# uart_key.net
KiCad netlist of a schematic drawn in Altium Designer
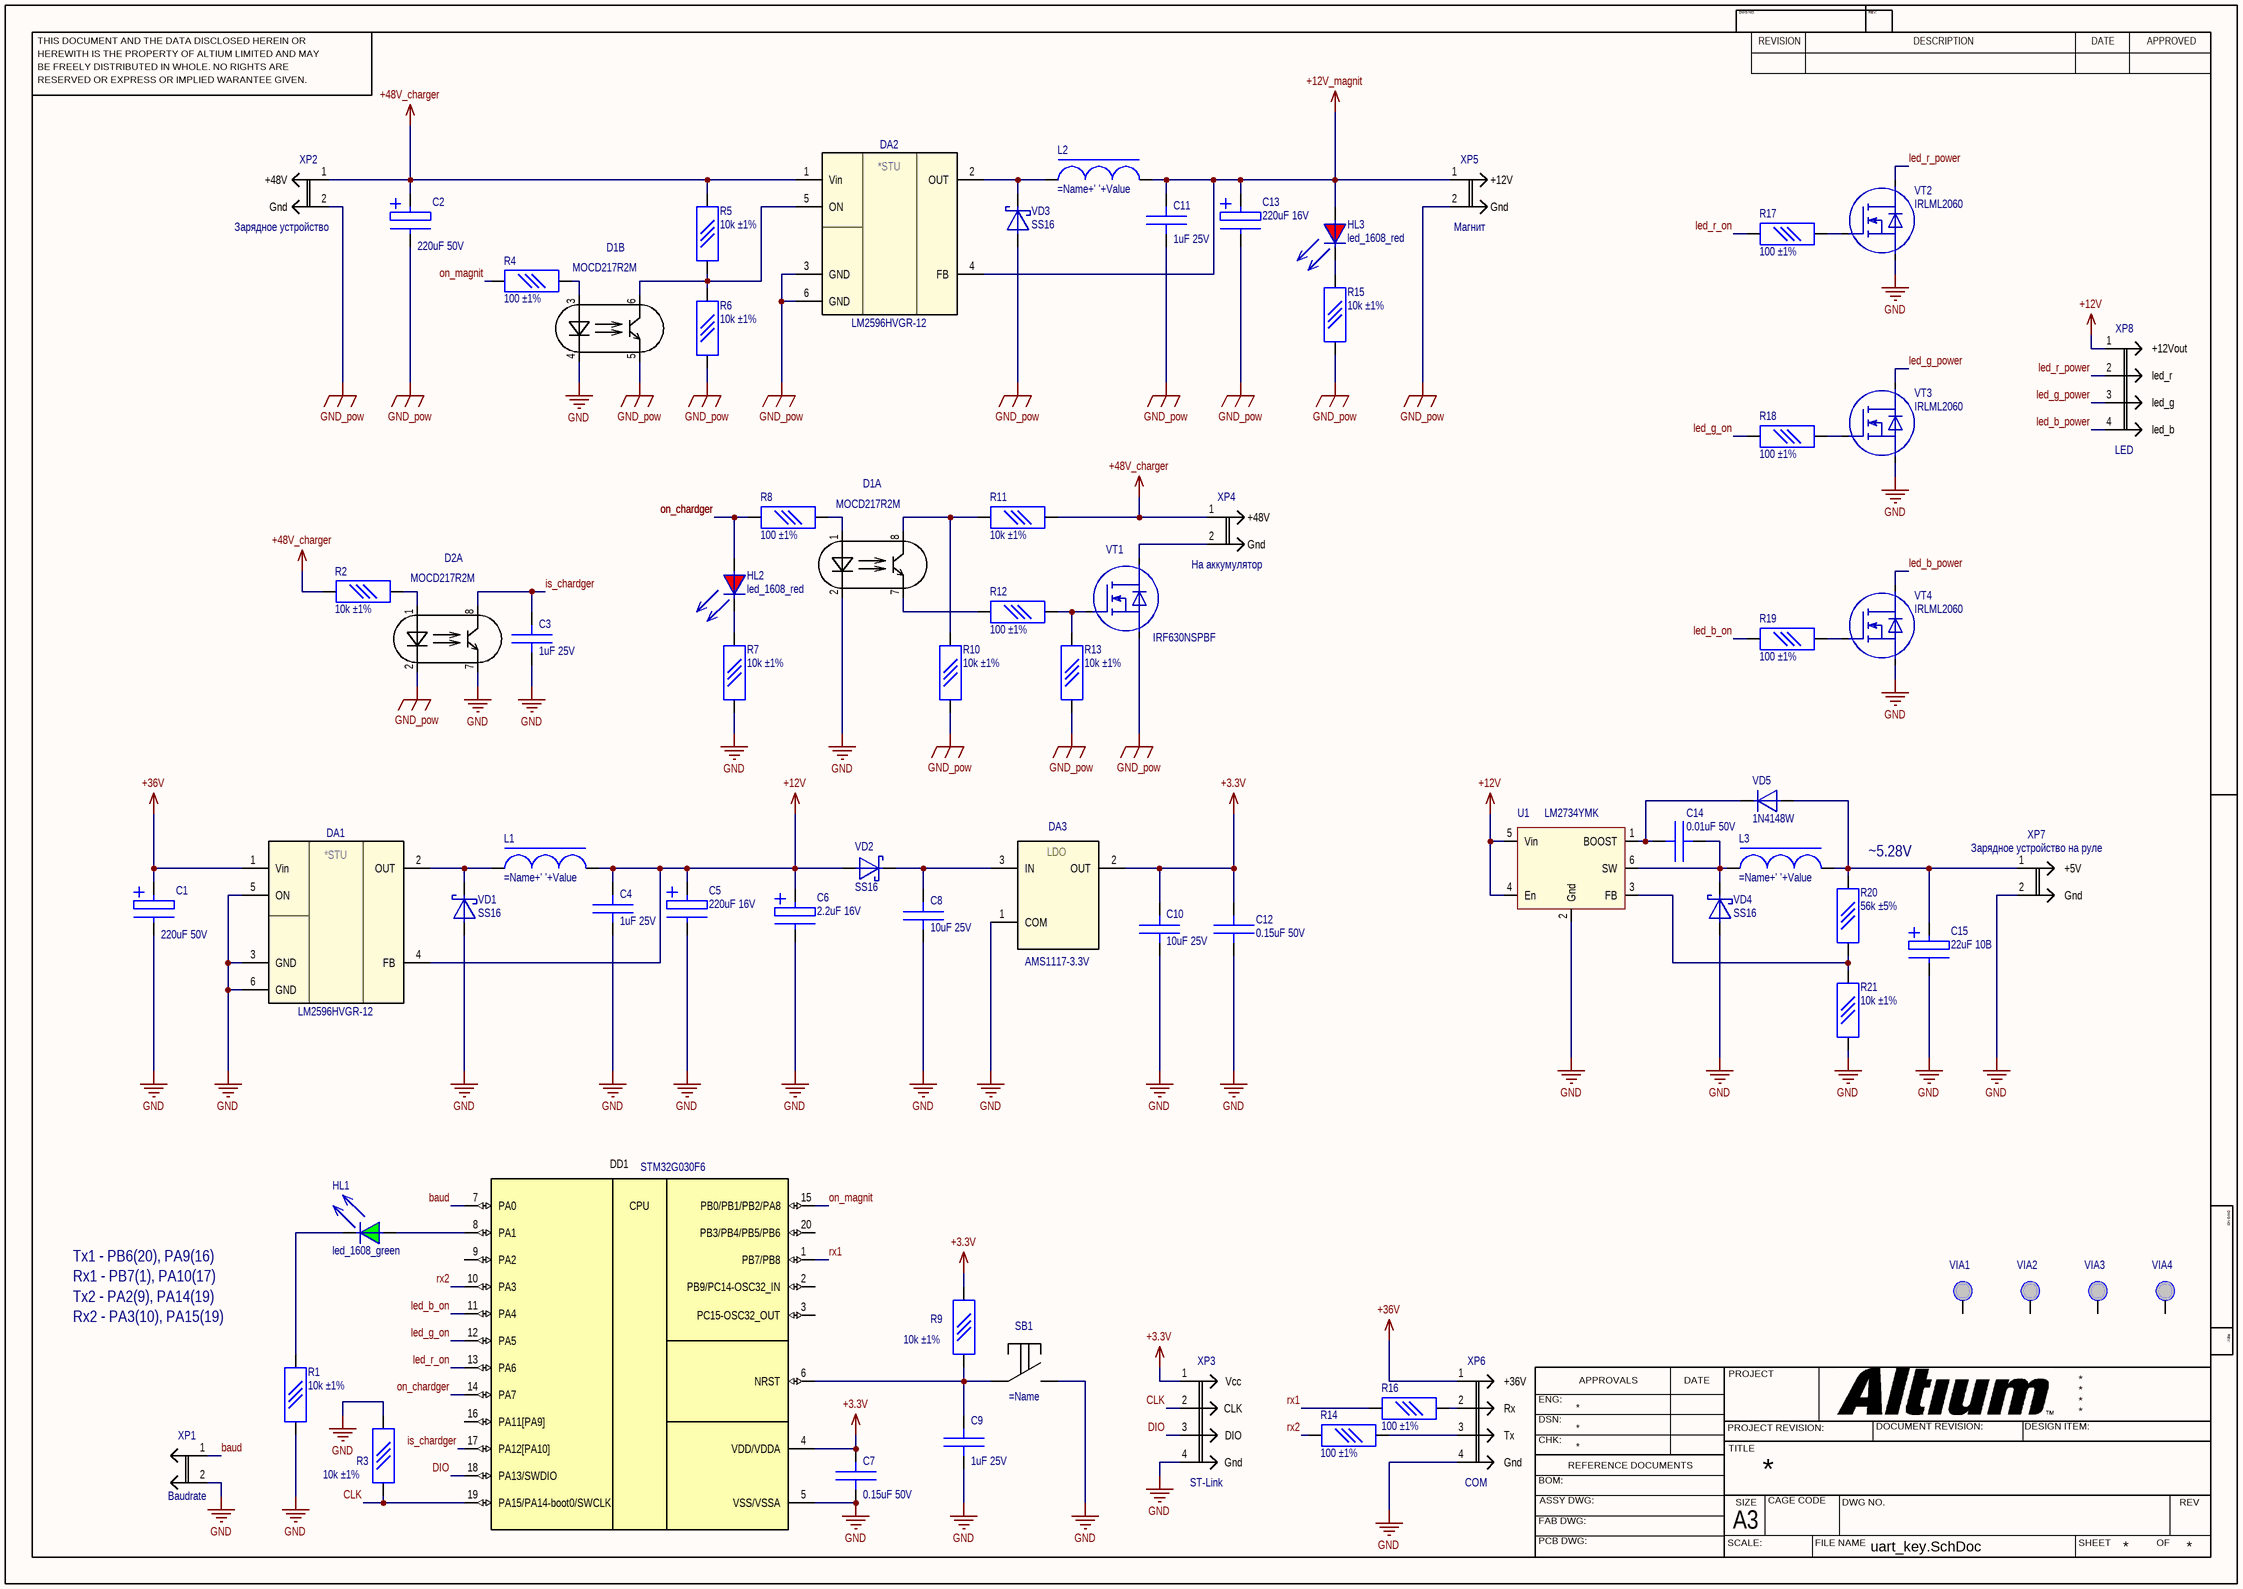
[diagram p0: uart_key.SchDoc]

(export (version "E")
  (design (tool "Eeschema 10.0.6"))
  (components
    (comp (ref "C1")
      (value "220uF 50V")
      (footprint "CAPAE_SMD_1010")
      (fields (field (name "VOLTAGE") "50V") (field (name "TOLERANCE") "±10%"))
      (libsource (lib "AD_lib") (part "Capacitor_elec"))
    )
    (comp (ref "C2")
      (value "220uF 50V")
      (footprint "CAPAE_SMD_1010")
      (fields (field (name "VOLTAGE") "50V") (field (name "TOLERANCE") "±10%"))
      (libsource (lib "AD_lib") (part "Capacitor_elec"))
    )
    (comp (ref "C3")
      (value "1uF 25V")
      (footprint "CC0603_0.8mm")
      (fields (field (name "VOLTAGE") "25V") (field (name "TOLERANCE") "±10%"))
      (libsource (lib "AD_lib") (part "Capacitor"))
    )
    (comp (ref "C4")
      (value "1uF 25V")
      (footprint "CC0603_0.8mm")
      (fields (field (name "VOLTAGE") "25V") (field (name "TOLERANCE") "±10%"))
      (libsource (lib "AD_lib") (part "Capacitor"))
    )
    (comp (ref "C5")
      (value "220uF 16V")
      (footprint "CAPAE_SMD_0607")
      (fields (field (name "VOLTAGE") "16V") (field (name "TOLERANCE") "±10%"))
      (libsource (lib "AD_lib") (part "Capacitor_elec"))
    )
    (comp (ref "C6")
      (value "2.2uF 16V")
      (footprint "TANT_3.2X1.6_A")
      (fields (field (name "VOLTAGE") "16V") (field (name "TOLERANCE") "±10%"))
      (libsource (lib "AD_lib") (part "Capacitor_elec"))
    )
    (comp (ref "C7")
      (value "0.15uF 50V")
      (footprint "CC0603_0.8mm")
      (fields (field (name "VOLTAGE") "50V") (field (name "TOLERANCE") "±10%"))
      (libsource (lib "AD_lib") (part "Capacitor"))
    )
    (comp (ref "C8")
      (value "10uF 25V")
      (footprint "CC0603_0.8mm")
      (fields (field (name "VOLTAGE") "25V") (field (name "TOLERANCE") "±10%"))
      (libsource (lib "AD_lib") (part "Capacitor"))
    )
    (comp (ref "C9")
      (value "1uF 25V")
      (footprint "CC0603_0.8mm")
      (fields (field (name "VOLTAGE") "25V") (field (name "TOLERANCE") "±10%"))
      (libsource (lib "AD_lib") (part "Capacitor"))
    )
    (comp (ref "C10")
      (value "10uF 25V")
      (footprint "CC0603_0.8mm")
      (fields (field (name "VOLTAGE") "25V") (field (name "TOLERANCE") "±10%"))
      (libsource (lib "AD_lib") (part "Capacitor"))
    )
    (comp (ref "C11")
      (value "1uF 25V")
      (footprint "CC0603_0.8mm")
      (fields (field (name "VOLTAGE") "25V") (field (name "TOLERANCE") "±10%"))
      (libsource (lib "AD_lib") (part "Capacitor"))
    )
    (comp (ref "C12")
      (value "0.15uF 50V")
      (footprint "CC0603_0.8mm")
      (fields (field (name "VOLTAGE") "50V") (field (name "TOLERANCE") "±10%"))
      (libsource (lib "AD_lib") (part "Capacitor"))
    )
    (comp (ref "C13")
      (value "220uF 16V")
      (footprint "CAPAE_SMD_0607")
      (fields (field (name "VOLTAGE") "16V") (field (name "TOLERANCE") "±10%"))
      (libsource (lib "AD_lib") (part "Capacitor_elec"))
    )
    (comp (ref "C14")
      (value "0.01uF 50V")
      (footprint "CC0603_0.8mm")
      (fields (field (name "VOLTAGE") "50V") (field (name "TOLERANCE") "±10%"))
      (libsource (lib "AD_lib") (part "Capacitor"))
    )
    (comp (ref "C15")
      (value "22uF 10В")
      (footprint "TANT_3.5X2.8_B")
      (fields (field (name "VOLTAGE") "10В") (field (name "TOLERANCE") "±10%"))
      (libsource (lib "AD_lib") (part "Capacitor_elec"))
    )
    (comp (ref "D1")
      (value "MOCD217R2M")
      (footprint "SO-8_height")
      (libsource (lib "AD_lib") (part "MOCD217R2M"))
    )
    (comp (ref "D2")
      (value "MOCD217R2M")
      (footprint "SO-8_height")
      (libsource (lib "AD_lib") (part "MOCD217R2M"))
    )
    (comp (ref "DA1")
      (value "LM2596HVGR-12")
      (footprint "TO-263-5 (D2PAK)_2_thermal_pad")
      (libsource (lib "AD_lib") (part "LM2596HVGR-12"))
    )
    (comp (ref "DA2")
      (value "LM2596HVGR-12")
      (footprint "TO-263-5 (D2PAK)_2_thermal_pad")
      (libsource (lib "AD_lib") (part "LM2596HVGR-12"))
    )
    (comp (ref "DA3")
      (value "AMS1117-3.3V")
      (footprint "SOT-223")
      (libsource (lib "AD_lib") (part "AMS1117-___V"))
    )
    (comp (ref "DD1")
      (value "STM32G030F6")
      (footprint "TSSOP-20_ST")
      (libsource (lib "AD_lib") (part "STM32G030F6"))
    )
    (comp (ref "HL1")
      (value "led_1608_green")
      (footprint "led_1608")
      (libsource (lib "AD_lib") (part "led_1608_green"))
    )
    (comp (ref "HL2")
      (value "led_1608_red")
      (footprint "led_1608")
      (libsource (lib "AD_lib") (part "led_1608_red"))
    )
    (comp (ref "HL3")
      (value "led_1608_red")
      (footprint "led_1608")
      (libsource (lib "AD_lib") (part "led_1608_red"))
    )
    (comp (ref "L1") (value "33uH") (footprint "SDR1006") (libsource (lib "AD_lib") (part "Inductor")))
    (comp (ref "L2") (value "33uH") (footprint "SDR1006") (libsource (lib "AD_lib") (part "Inductor")))
    (comp (ref "L3") (value "10uH") (footprint "SDR0604") (libsource (lib "AD_lib") (part "Inductor")))
    (comp (ref "R1")
      (value "10k ±1%")
      (footprint "R0603")
      (fields (field (name "TOLERANCE") "±1%"))
      (libsource (lib "AD_lib") (part "Res_0603"))
    )
    (comp (ref "R2")
      (value "10k ±1%")
      (footprint "R0603")
      (fields (field (name "TOLERANCE") "±1%"))
      (libsource (lib "AD_lib") (part "Res_0603"))
    )
    (comp (ref "R3")
      (value "10k ±1%")
      (footprint "R0603")
      (fields (field (name "TOLERANCE") "±1%"))
      (libsource (lib "AD_lib") (part "Res_0603"))
    )
    (comp (ref "R4")
      (value "100 ±1%")
      (footprint "R0603")
      (fields (field (name "TOLERANCE") "±1%"))
      (libsource (lib "AD_lib") (part "Res_0603"))
    )
    (comp (ref "R5")
      (value "10k ±1%")
      (footprint "R0603")
      (fields (field (name "TOLERANCE") "±1%"))
      (libsource (lib "AD_lib") (part "Res_0603"))
    )
    (comp (ref "R6")
      (value "10k ±1%")
      (footprint "R0603")
      (fields (field (name "TOLERANCE") "±1%"))
      (libsource (lib "AD_lib") (part "Res_0603"))
    )
    (comp (ref "R7")
      (value "10k ±1%")
      (footprint "R0603")
      (fields (field (name "TOLERANCE") "±1%"))
      (libsource (lib "AD_lib") (part "Res_0603"))
    )
    (comp (ref "R8")
      (value "100 ±1%")
      (footprint "R0603")
      (fields (field (name "TOLERANCE") "±1%"))
      (libsource (lib "AD_lib") (part "Res_0603"))
    )
    (comp (ref "R9")
      (value "10k ±1%")
      (footprint "R0603")
      (fields (field (name "TOLERANCE") "±1%"))
      (libsource (lib "AD_lib") (part "Res_0603"))
    )
    (comp (ref "R10")
      (value "10k ±1%")
      (footprint "R0603")
      (fields (field (name "TOLERANCE") "±1%"))
      (libsource (lib "AD_lib") (part "Res_0603"))
    )
    (comp (ref "R11")
      (value "10k ±1%")
      (footprint "R0603")
      (fields (field (name "TOLERANCE") "±1%"))
      (libsource (lib "AD_lib") (part "Res_0603"))
    )
    (comp (ref "R12")
      (value "100 ±1%")
      (footprint "R0603")
      (fields (field (name "TOLERANCE") "±1%"))
      (libsource (lib "AD_lib") (part "Res_0603"))
    )
    (comp (ref "R13")
      (value "10k ±1%")
      (footprint "R0603")
      (fields (field (name "TOLERANCE") "±1%"))
      (libsource (lib "AD_lib") (part "Res_0603"))
    )
    (comp (ref "R14")
      (value "100 ±1%")
      (footprint "R0603")
      (fields (field (name "TOLERANCE") "±1%"))
      (libsource (lib "AD_lib") (part "Res_0603"))
    )
    (comp (ref "R15")
      (value "10k ±1%")
      (footprint "R0603")
      (fields (field (name "TOLERANCE") "±1%"))
      (libsource (lib "AD_lib") (part "Res_0603"))
    )
    (comp (ref "R16")
      (value "100 ±1%")
      (footprint "R0603")
      (fields (field (name "TOLERANCE") "±1%"))
      (libsource (lib "AD_lib") (part "Res_0603"))
    )
    (comp (ref "R17")
      (value "100 ±1%")
      (footprint "R0603")
      (fields (field (name "TOLERANCE") "±1%"))
      (libsource (lib "AD_lib") (part "Res_0603"))
    )
    (comp (ref "R18")
      (value "100 ±1%")
      (footprint "R0603")
      (fields (field (name "TOLERANCE") "±1%"))
      (libsource (lib "AD_lib") (part "Res_0603"))
    )
    (comp (ref "R19")
      (value "100 ±1%")
      (footprint "R0603")
      (fields (field (name "TOLERANCE") "±1%"))
      (libsource (lib "AD_lib") (part "Res_0603"))
    )
    (comp (ref "R20")
      (value "56k ±5%")
      (footprint "R0603")
      (fields (field (name "TOLERANCE") "±5%"))
      (libsource (lib "AD_lib") (part "Res_0603"))
    )
    (comp (ref "R21")
      (value "10k ±1%")
      (footprint "R0603")
      (fields (field (name "TOLERANCE") "±1%"))
      (libsource (lib "AD_lib") (part "Res_0603"))
    )
    (comp (ref "SB1")
      (value "~")
      (footprint "KLS7-TS3401_4х3х2,5")
      (libsource (lib "AD_lib") (part "Tact_4х3х2.5_SMD"))
    )
    (comp (ref "U1") (value "LM2734YMK") (footprint "SOT-23-6") (libsource (lib "AD_lib") (part "LM2734YMK")))
    (comp (ref "VD1") (value "SS16") (footprint "DO-214AC (SMA)") (libsource (lib "AD_lib") (part "SS16")))
    (comp (ref "VD2") (value "SS16") (footprint "DO-214AC (SMA)") (libsource (lib "AD_lib") (part "SS16")))
    (comp (ref "VD3") (value "SS16") (footprint "DO-214AC (SMA)") (libsource (lib "AD_lib") (part "SS16")))
    (comp (ref "VD4") (value "SS16") (footprint "DO-214AC (SMA)") (libsource (lib "AD_lib") (part "SS16")))
    (comp (ref "VD5") (value "1N4148W") (footprint "SOD-123") (libsource (lib "AD_lib") (part "Diode")))
    (comp (ref "VIA1")
      (value "via_circle_2.2mm")
      (footprint "via_circle_2.2")
      (libsource (lib "AD_lib") (part "via_circle_2.2mm"))
    )
    (comp (ref "VIA2")
      (value "via_circle_2.2mm")
      (footprint "via_circle_2.2")
      (libsource (lib "AD_lib") (part "via_circle_2.2mm"))
    )
    (comp (ref "VIA3")
      (value "via_circle_2.2mm")
      (footprint "via_circle_2.2")
      (libsource (lib "AD_lib") (part "via_circle_2.2mm"))
    )
    (comp (ref "VIA4")
      (value "via_circle_2.2mm")
      (footprint "via_circle_2.2")
      (libsource (lib "AD_lib") (part "via_circle_2.2mm"))
    )
    (comp (ref "VT1")
      (value "IRF630NSPBF")
      (footprint "TO-263A (D2PAK)_thermal_pad")
      (libsource (lib "AD_lib") (part "IRF630NSPBF"))
    )
    (comp (ref "VT2") (value "IRLML2060") (footprint "SOT-23") (libsource (lib "AD_lib") (part "IRLML2060")))
    (comp (ref "VT3") (value "IRLML2060") (footprint "SOT-23") (libsource (lib "AD_lib") (part "IRLML2060")))
    (comp (ref "VT4") (value "IRLML2060") (footprint "SOT-23") (libsource (lib "AD_lib") (part "IRLML2060")))
    (comp (ref "XP1")
      (value "Baudrate")
      (footprint "PLS-2")
      (libsource (lib "AD_lib") (part "Conn_01_02pin"))
    )
    (comp (ref "XP2")
      (value "Зарядное устройство")
      (footprint "DG308x2")
      (fields (field (name "CIRCUIT_1") "+48V") (field (name "CIRCUIT_2") "Gnd"))
      (libsource (lib "AD_lib") (part "DG308x2"))
    )
    (comp (ref "XP3")
      (value "ST-Link")
      (footprint "B4B-ZR")
      (fields
        (field (name "CIRCUIT_1") "Vcc")
        (field (name "CIRCUIT_2") "CLK")
        (field (name "CIRCUIT_3") "DIO")
        (field (name "CIRCUIT_4") "Gnd")
      )
      (libsource (lib "AD_lib") (part "B4B-ZR_conn_01x04_st_link"))
    )
    (comp (ref "XP4")
      (value "На аккумулятор")
      (footprint "DG308x2")
      (fields (field (name "CIRCUIT_1") "+48V") (field (name "CIRCUIT_2") "Gnd"))
      (libsource (lib "AD_lib") (part "DG308x2"))
    )
    (comp (ref "XP5")
      (value "Магнит")
      (footprint "DG308x2")
      (fields (field (name "CIRCUIT_1") "+12V") (field (name "CIRCUIT_2") "Gnd"))
      (libsource (lib "AD_lib") (part "DG308x2"))
    )
    (comp (ref "XP6")
      (value "COM")
      (footprint "JST_XH_B4B-XH-A_1x04_P2.50mm_Vertical")
      (fields
        (field (name "CIRCUIT_1") "+36V")
        (field (name "CIRCUIT_2") "Rx")
        (field (name "CIRCUIT_3") "Tx")
        (field (name "CIRCUIT_4") "Gnd")
      )
      (libsource (lib "AD_lib") (part "JST_XH_B4B-XH-A_1x04_P2.50mm_Vertical"))
    )
    (comp (ref "XP7")
      (value "Зарядное устройство на руле")
      (footprint "B2B-XH-A")
      (fields (field (name "+5V") "+5V") (field (name "CIRCUIT_2") "Gnd"))
      (libsource (lib "AD_lib") (part "Conn_01_02pin"))
    )
    (comp (ref "XP8")
      (value "LED")
      (footprint "JST_XH_B4B-XH-A_1x04_P2.50mm_Vertical")
      (fields
        (field (name "CIRCUIT_1") "+12Vout")
        (field (name "CIRCUIT_2") "led_r")
        (field (name "CIRCUIT_3") "led_g")
        (field (name "CIRCUIT_4") "led_b")
      )
      (libsource (lib "AD_lib") (part "JST_XH_B4B-XH-A_1x04_P2.50mm_Vertical"))
    )
  )
  (nets
    (net (code "1") (name "+3.3V") (class "Default")
      (node (ref "C10") (pin "1") (pintype "passive"))
      (node (ref "C12") (pin "1") (pintype "passive"))
      (node (ref "C7") (pin "1") (pintype "passive"))
      (node (ref "DA3") (pin "2") (pinfunction "OUT_2") (pintype "passive"))
      (node (ref "DD1") (pin "4") (pinfunction "VDD/VDDA_4") (pintype "power_in"))
      (node (ref "R9") (pin "1") (pinfunction "BOT_1") (pintype "passive"))
      (node (ref "XP3") (pin "1") (pinfunction "1_1") (pintype "passive"))
    )
    (net (code "2") (name "+12V") (class "Default")
      (node (ref "C4") (pin "1") (pintype "passive"))
      (node (ref "C5") (pin "2") (pinfunction "+_2") (pintype "passive"))
      (node (ref "C6") (pin "2") (pinfunction "+_2") (pintype "passive"))
      (node (ref "DA1") (pin "4") (pinfunction "FB_4") (pintype "passive"))
      (node (ref "L1") (pin "2") (pintype "passive"))
      (node (ref "U1") (pin "4") (pinfunction "En_4") (pintype "passive"))
      (node (ref "U1") (pin "5") (pinfunction "Vin_5") (pintype "passive"))
      (node (ref "VD2") (pin "2") (pinfunction "A_2") (pintype "passive"))
      (node (ref "XP8") (pin "1") (pinfunction "1_1") (pintype "passive"))
    )
    (net (code "3") (name "+12V_magnit") (class "Default")
      (node (ref "C11") (pin "1") (pintype "passive"))
      (node (ref "C13") (pin "2") (pinfunction "+_2") (pintype "passive"))
      (node (ref "DA2") (pin "4") (pinfunction "FB_4") (pintype "passive"))
      (node (ref "HL3") (pin "2") (pinfunction "A_2") (pintype "passive"))
      (node (ref "L2") (pin "2") (pintype "passive"))
      (node (ref "XP5") (pin "1") (pinfunction "1_1") (pintype "passive"))
    )
    (net (code "4") (name "+36V") (class "Default")
      (node (ref "C1") (pin "2") (pinfunction "+_2") (pintype "passive"))
      (node (ref "DA1") (pin "1") (pinfunction "Vin_1") (pintype "passive"))
      (node (ref "XP6") (pin "1") (pinfunction "1_1") (pintype "passive"))
    )
    (net (code "5") (name "+48V_charger") (class "Default")
      (node (ref "C2") (pin "2") (pinfunction "+_2") (pintype "passive"))
      (node (ref "DA2") (pin "1") (pinfunction "Vin_1") (pintype "passive"))
      (node (ref "R11") (pin "2") (pinfunction "TOP_2") (pintype "passive"))
      (node (ref "R2") (pin "2") (pinfunction "TOP_2") (pintype "passive"))
      (node (ref "R5") (pin "1") (pinfunction "BOT_1") (pintype "passive"))
      (node (ref "XP2") (pin "1") (pinfunction "1_1") (pintype "passive"))
      (node (ref "XP4") (pin "1") (pinfunction "1_1") (pintype "passive"))
    )
    (net (code "6") (name "/CLK") (class "Default")
      (node (ref "DD1") (pin "19") (pinfunction "PA15/PA14-boot0/SWCLK_19") (pintype "bidirectional"))
      (node (ref "R3") (pin "2") (pinfunction "TOP_2") (pintype "passive"))
      (node (ref "XP3") (pin "2") (pinfunction "2_2") (pintype "passive"))
    )
    (net (code "7") (name "/DIO") (class "Default")
      (node (ref "DD1") (pin "18") (pinfunction "PA13/SWDIO_18") (pintype "bidirectional"))
      (node (ref "XP3") (pin "3") (pinfunction "3_3") (pintype "passive"))
    )
    (net (code "8") (name "/baud") (class "Default")
      (node (ref "DD1") (pin "7") (pinfunction "PA0_7") (pintype "bidirectional"))
      (node (ref "XP1") (pin "1") (pinfunction "1_1") (pintype "passive"))
    )
    (net (code "9") (name "/is_chardger") (class "Default")
      (node (ref "C3") (pin "1") (pintype "passive"))
      (node (ref "D2") (pin "8") (pinfunction "8_8") (pintype "passive"))
      (node (ref "DD1") (pin "17") (pinfunction "PA12[PA10]_17") (pintype "bidirectional"))
    )
    (net (code "10") (name "/led_b_on") (class "Default")
      (node (ref "DD1") (pin "11") (pinfunction "PA4_11") (pintype "bidirectional"))
      (node (ref "R19") (pin "1") (pinfunction "BOT_1") (pintype "passive"))
    )
    (net (code "11") (name "/led_b_power") (class "Default")
      (node (ref "VT4") (pin "3") (pinfunction "D_3") (pintype "passive"))
      (node (ref "XP8") (pin "4") (pinfunction "4_4") (pintype "passive"))
    )
    (net (code "12") (name "/led_g_on") (class "Default")
      (node (ref "DD1") (pin "12") (pinfunction "PA5_12") (pintype "bidirectional"))
      (node (ref "R18") (pin "1") (pinfunction "BOT_1") (pintype "passive"))
    )
    (net (code "13") (name "/led_g_power") (class "Default")
      (node (ref "VT3") (pin "3") (pinfunction "D_3") (pintype "passive"))
      (node (ref "XP8") (pin "3") (pinfunction "3_3") (pintype "passive"))
    )
    (net (code "14") (name "/led_r_on") (class "Default")
      (node (ref "DD1") (pin "13") (pinfunction "PA6_13") (pintype "bidirectional"))
      (node (ref "R17") (pin "1") (pinfunction "BOT_1") (pintype "passive"))
    )
    (net (code "15") (name "/led_r_power") (class "Default")
      (node (ref "VT2") (pin "3") (pinfunction "D_3") (pintype "passive"))
      (node (ref "XP8") (pin "2") (pinfunction "2_2") (pintype "passive"))
    )
    (net (code "16") (name "/on_chardger") (class "Default")
      (node (ref "DD1") (pin "14") (pinfunction "PA7_14") (pintype "bidirectional"))
      (node (ref "HL2") (pin "2") (pinfunction "A_2") (pintype "passive"))
      (node (ref "R8") (pin "1") (pinfunction "BOT_1") (pintype "passive"))
    )
    (net (code "17") (name "/on_magnit") (class "Default")
      (node (ref "DD1") (pin "15") (pinfunction "PB0/PB1/PB2/PA8_15") (pintype "bidirectional"))
      (node (ref "R4") (pin "1") (pinfunction "BOT_1") (pintype "passive"))
    )
    (net (code "18") (name "/rx1") (class "Default")
      (node (ref "DD1") (pin "1") (pinfunction "PB7/PB8_1") (pintype "bidirectional"))
      (node (ref "R16") (pin "1") (pinfunction "BOT_1") (pintype "passive"))
    )
    (net (code "19") (name "/rx2") (class "Default")
      (node (ref "DD1") (pin "10") (pinfunction "PA3_10") (pintype "bidirectional"))
      (node (ref "R14") (pin "1") (pinfunction "BOT_1") (pintype "passive"))
    )
    (net (code "20") (name "GND") (class "Default")
      (node (ref "C1") (pin "1") (pinfunction "-_1") (pintype "passive"))
      (node (ref "C10") (pin "2") (pintype "passive"))
      (node (ref "C12") (pin "2") (pintype "passive"))
      (node (ref "C15") (pin "1") (pinfunction "-_1") (pintype "passive"))
      (node (ref "C3") (pin "2") (pintype "passive"))
      (node (ref "C4") (pin "2") (pintype "passive"))
      (node (ref "C5") (pin "1") (pinfunction "-_1") (pintype "passive"))
      (node (ref "C6") (pin "1") (pinfunction "-_1") (pintype "passive"))
      (node (ref "C7") (pin "2") (pintype "passive"))
      (node (ref "C8") (pin "2") (pintype "passive"))
      (node (ref "C9") (pin "2") (pintype "passive"))
      (node (ref "D1") (pin "2") (pinfunction "2_2") (pintype "passive"))
      (node (ref "D1") (pin "4") (pinfunction "4_4") (pintype "passive"))
      (node (ref "D2") (pin "7") (pinfunction "7_7") (pintype "passive"))
      (node (ref "DA1") (pin "3") (pinfunction "GND_3") (pintype "passive"))
      (node (ref "DA1") (pin "5") (pinfunction "ON_5") (pintype "passive"))
      (node (ref "DA1") (pin "6") (pinfunction "GND_6") (pintype "passive"))
      (node (ref "DA3") (pin "1") (pinfunction "COM_1") (pintype "passive"))
      (node (ref "DD1") (pin "5") (pinfunction "VSS/VSSA_5") (pintype "power_in"))
      (node (ref "R1") (pin "2") (pinfunction "TOP_2") (pintype "passive"))
      (node (ref "R21") (pin "2") (pinfunction "TOP_2") (pintype "passive"))
      (node (ref "R3") (pin "1") (pinfunction "BOT_1") (pintype "passive"))
      (node (ref "R7") (pin "2") (pinfunction "TOP_2") (pintype "passive"))
      (node (ref "SB1") (pin "NO") (pinfunction "NO_NO") (pintype "passive"))
      (node (ref "U1") (pin "2") (pinfunction "Gnd_2") (pintype "passive"))
      (node (ref "VD1") (pin "2") (pinfunction "A_2") (pintype "passive"))
      (node (ref "VD4") (pin "2") (pinfunction "A_2") (pintype "passive"))
      (node (ref "VT2") (pin "2") (pinfunction "S_2") (pintype "passive"))
      (node (ref "VT3") (pin "2") (pinfunction "S_2") (pintype "passive"))
      (node (ref "VT4") (pin "2") (pinfunction "S_2") (pintype "passive"))
      (node (ref "XP1") (pin "2") (pinfunction "2_2") (pintype "passive"))
      (node (ref "XP3") (pin "4") (pinfunction "4_4") (pintype "passive"))
      (node (ref "XP6") (pin "4") (pinfunction "4_4") (pintype "passive"))
      (node (ref "XP7") (pin "2") (pinfunction "2_2") (pintype "passive"))
    )
    (net (code "21") (name "GND_pow") (class "Default")
      (node (ref "C11") (pin "2") (pintype "passive"))
      (node (ref "C13") (pin "1") (pinfunction "-_1") (pintype "passive"))
      (node (ref "C2") (pin "1") (pinfunction "-_1") (pintype "passive"))
      (node (ref "D1") (pin "5") (pinfunction "5_5") (pintype "passive"))
      (node (ref "D2") (pin "2") (pinfunction "2_2") (pintype "passive"))
      (node (ref "DA2") (pin "3") (pinfunction "GND_3") (pintype "passive"))
      (node (ref "DA2") (pin "6") (pinfunction "GND_6") (pintype "passive"))
      (node (ref "R10") (pin "2") (pinfunction "TOP_2") (pintype "passive"))
      (node (ref "R13") (pin "2") (pinfunction "TOP_2") (pintype "passive"))
      (node (ref "R15") (pin "2") (pinfunction "TOP_2") (pintype "passive"))
      (node (ref "R6") (pin "2") (pinfunction "TOP_2") (pintype "passive"))
      (node (ref "VD3") (pin "2") (pinfunction "A_2") (pintype "passive"))
      (node (ref "VT1") (pin "3") (pinfunction "S_3") (pintype "passive"))
      (node (ref "XP2") (pin "2") (pinfunction "2_2") (pintype "passive"))
      (node (ref "XP5") (pin "2") (pinfunction "2_2") (pintype "passive"))
    )
    (net (code "22") (name "Net-(C15-+)") (class "Default")
      (node (ref "C15") (pin "2") (pinfunction "+_2") (pintype "passive"))
      (node (ref "L3") (pin "2") (pintype "passive"))
      (node (ref "R20") (pin "1") (pinfunction "BOT_1") (pintype "passive"))
      (node (ref "VD5") (pin "2") (pinfunction "A_2") (pintype "passive"))
      (node (ref "XP7") (pin "1") (pinfunction "1_1") (pintype "passive"))
    )
    (net (code "23") (name "Net-(DA1-OUT)") (class "Default")
      (node (ref "DA1") (pin "2") (pinfunction "OUT_2") (pintype "passive"))
      (node (ref "L1") (pin "1") (pintype "passive"))
      (node (ref "VD1") (pin "1") (pinfunction "C_1") (pintype "passive"))
    )
    (net (code "24") (name "Net-(DA2-ON)") (class "Default")
      (node (ref "D1") (pin "6") (pinfunction "6_6") (pintype "passive"))
      (node (ref "DA2") (pin "5") (pinfunction "ON_5") (pintype "passive"))
      (node (ref "R5") (pin "2") (pinfunction "TOP_2") (pintype "passive"))
      (node (ref "R6") (pin "1") (pinfunction "BOT_1") (pintype "passive"))
    )
    (net (code "25") (name "Net-(DA2-OUT)") (class "Default")
      (node (ref "DA2") (pin "2") (pinfunction "OUT_2") (pintype "passive"))
      (node (ref "L2") (pin "1") (pintype "passive"))
      (node (ref "VD3") (pin "1") (pinfunction "C_1") (pintype "passive"))
    )
    (net (code "26") (name "Net-(DA3-IN)") (class "Default")
      (node (ref "C8") (pin "1") (pintype "passive"))
      (node (ref "DA3") (pin "3") (pinfunction "IN_3") (pintype "passive"))
      (node (ref "VD2") (pin "1") (pinfunction "C_1") (pintype "passive"))
    )
    (net (code "27") (name "Net-(DD1-NRST)") (class "Default")
      (node (ref "C9") (pin "1") (pintype "passive"))
      (node (ref "DD1") (pin "6") (pinfunction "NRST_6") (pintype "bidirectional"))
      (node (ref "R9") (pin "2") (pinfunction "TOP_2") (pintype "passive"))
      (node (ref "SB1") (pin "COM") (pinfunction "COM_COM") (pintype "passive"))
    )
    (net (code "28") (name "Net-(DD1-PA1)") (class "Default")
      (node (ref "DD1") (pin "8") (pinfunction "PA1_8") (pintype "bidirectional"))
      (node (ref "HL1") (pin "2") (pinfunction "A_2") (pintype "passive"))
    )
    (net (code "29") (name "Net-(HL1-C)") (class "Default")
      (node (ref "HL1") (pin "1") (pinfunction "C_1") (pintype "passive"))
      (node (ref "R1") (pin "1") (pinfunction "BOT_1") (pintype "passive"))
    )
    (net (code "30") (name "Net-(HL2-C)") (class "Default")
      (node (ref "HL2") (pin "1") (pinfunction "C_1") (pintype "passive"))
      (node (ref "R7") (pin "1") (pinfunction "BOT_1") (pintype "passive"))
    )
    (net (code "31") (name "Net-(HL3-C)") (class "Default")
      (node (ref "HL3") (pin "1") (pinfunction "C_1") (pintype "passive"))
      (node (ref "R15") (pin "1") (pinfunction "BOT_1") (pintype "passive"))
    )
    (net (code "32") (name "Net-(R2-BOT)") (class "Default")
      (node (ref "D2") (pin "1") (pinfunction "1_1") (pintype "passive"))
      (node (ref "R2") (pin "1") (pinfunction "BOT_1") (pintype "passive"))
    )
    (net (code "33") (name "Net-(R4-TOP)") (class "Default")
      (node (ref "D1") (pin "3") (pinfunction "3_3") (pintype "passive"))
      (node (ref "R4") (pin "2") (pinfunction "TOP_2") (pintype "passive"))
    )
    (net (code "34") (name "Net-(R8-TOP)") (class "Default")
      (node (ref "D1") (pin "1") (pinfunction "1_1") (pintype "passive"))
      (node (ref "R8") (pin "2") (pinfunction "TOP_2") (pintype "passive"))
    )
    (net (code "35") (name "Net-(R10-BOT)") (class "Default")
      (node (ref "D1") (pin "8") (pinfunction "8_8") (pintype "passive"))
      (node (ref "R10") (pin "1") (pinfunction "BOT_1") (pintype "passive"))
      (node (ref "R11") (pin "1") (pinfunction "BOT_1") (pintype "passive"))
    )
    (net (code "36") (name "Net-(R12-BOT)") (class "Default")
      (node (ref "D1") (pin "7") (pinfunction "7_7") (pintype "passive"))
      (node (ref "R12") (pin "1") (pinfunction "BOT_1") (pintype "passive"))
    )
    (net (code "37") (name "Net-(R12-TOP)") (class "Default")
      (node (ref "R12") (pin "2") (pinfunction "TOP_2") (pintype "passive"))
      (node (ref "R13") (pin "1") (pinfunction "BOT_1") (pintype "passive"))
      (node (ref "VT1") (pin "1") (pinfunction "G_1") (pintype "passive"))
    )
    (net (code "38") (name "Net-(R14-TOP)") (class "Default")
      (node (ref "R14") (pin "2") (pinfunction "TOP_2") (pintype "passive"))
      (node (ref "XP6") (pin "3") (pinfunction "3_3") (pintype "passive"))
    )
    (net (code "39") (name "Net-(R16-TOP)") (class "Default")
      (node (ref "R16") (pin "2") (pinfunction "TOP_2") (pintype "passive"))
      (node (ref "XP6") (pin "2") (pinfunction "2_2") (pintype "passive"))
    )
    (net (code "40") (name "Net-(R17-TOP)") (class "Default")
      (node (ref "R17") (pin "2") (pinfunction "TOP_2") (pintype "passive"))
      (node (ref "VT2") (pin "1") (pinfunction "G_1") (pintype "passive"))
    )
    (net (code "41") (name "Net-(R18-TOP)") (class "Default")
      (node (ref "R18") (pin "2") (pinfunction "TOP_2") (pintype "passive"))
      (node (ref "VT3") (pin "1") (pinfunction "G_1") (pintype "passive"))
    )
    (net (code "42") (name "Net-(R19-TOP)") (class "Default")
      (node (ref "R19") (pin "2") (pinfunction "TOP_2") (pintype "passive"))
      (node (ref "VT4") (pin "1") (pinfunction "G_1") (pintype "passive"))
    )
    (net (code "43") (name "Net-(R20-TOP)") (class "Default")
      (node (ref "R20") (pin "2") (pinfunction "TOP_2") (pintype "passive"))
      (node (ref "R21") (pin "1") (pinfunction "BOT_1") (pintype "passive"))
      (node (ref "U1") (pin "3") (pinfunction "FB_3") (pintype "passive"))
    )
    (net (code "44") (name "Net-(U1-BOOST)") (class "Default")
      (node (ref "C14") (pin "1") (pintype "passive"))
      (node (ref "U1") (pin "1") (pinfunction "BOOST_1") (pintype "passive"))
      (node (ref "VD5") (pin "1") (pinfunction "C_1") (pintype "passive"))
    )
    (net (code "45") (name "Net-(U1-SW)") (class "Default")
      (node (ref "C14") (pin "2") (pintype "passive"))
      (node (ref "L3") (pin "1") (pintype "passive"))
      (node (ref "U1") (pin "6") (pinfunction "SW_6") (pintype "passive"))
      (node (ref "VD4") (pin "1") (pinfunction "C_1") (pintype "passive"))
    )
    (net (code "46") (name "Net-(VT1-D)") (class "Default")
      (node (ref "VT1") (pin "2") (pinfunction "D_2") (pintype "passive"))
      (node (ref "XP4") (pin "2") (pinfunction "2_2") (pintype "passive"))
    )
    (net (code "47") (name "unconnected-(DA1-Pad6)") (class "Default")
      (node (ref "DA1") (pin "6") (pintype "passive"))
    )
    (net (code "48") (name "unconnected-(DA2-Pad6)") (class "Default")
      (node (ref "DA2") (pin "6") (pintype "passive"))
    )
    (net (code "49") (name "unconnected-(DD1-PA2-Pad9)") (class "Default")
      (node (ref "DD1") (pin "9") (pinfunction "PA2_9") (pintype "bidirectional"))
    )
    (net (code "50") (name "unconnected-(DD1-PA11[PA9]-Pad16)") (class "Default")
      (node (ref "DD1") (pin "16") (pinfunction "PA11[PA9]_16") (pintype "bidirectional"))
    )
    (net (code "51") (name "unconnected-(DD1-PB3{slash}PB4{slash}PB5{slash}PB6-Pad20)") (class "Default")
      (node (ref "DD1") (pin "20") (pinfunction "PB3/PB4/PB5/PB6_20") (pintype "bidirectional"))
    )
    (net (code "52") (name "unconnected-(DD1-PB9{slash}PC14-OSC32_IN-Pad2)") (class "Default")
      (node (ref "DD1") (pin "2") (pinfunction "PB9/PC14-OSC32_IN_2") (pintype "bidirectional"))
    )
    (net (code "53") (name "unconnected-(DD1-PC15-OSC32_OUT-Pad3)") (class "Default")
      (node (ref "DD1") (pin "3") (pinfunction "PC15-OSC32_OUT_3") (pintype "bidirectional"))
    )
    (net (code "54") (name "unconnected-(VIA1-VIA?-Pad1)") (class "Default")
      (node (ref "VIA1") (pin "1") (pinfunction "VIA?_1") (pintype "passive"))
    )
    (net (code "55") (name "unconnected-(VIA2-VIA?-Pad1)") (class "Default")
      (node (ref "VIA2") (pin "1") (pinfunction "VIA?_1") (pintype "passive"))
    )
    (net (code "56") (name "unconnected-(VIA3-VIA?-Pad1)") (class "Default")
      (node (ref "VIA3") (pin "1") (pinfunction "VIA?_1") (pintype "passive"))
    )
    (net (code "57") (name "unconnected-(VIA4-VIA?-Pad1)") (class "Default")
      (node (ref "VIA4") (pin "1") (pinfunction "VIA?_1") (pintype "passive"))
    )
  )
)
